# CPU.net
KiCad netlist of a schematic drawn in Altium Designer
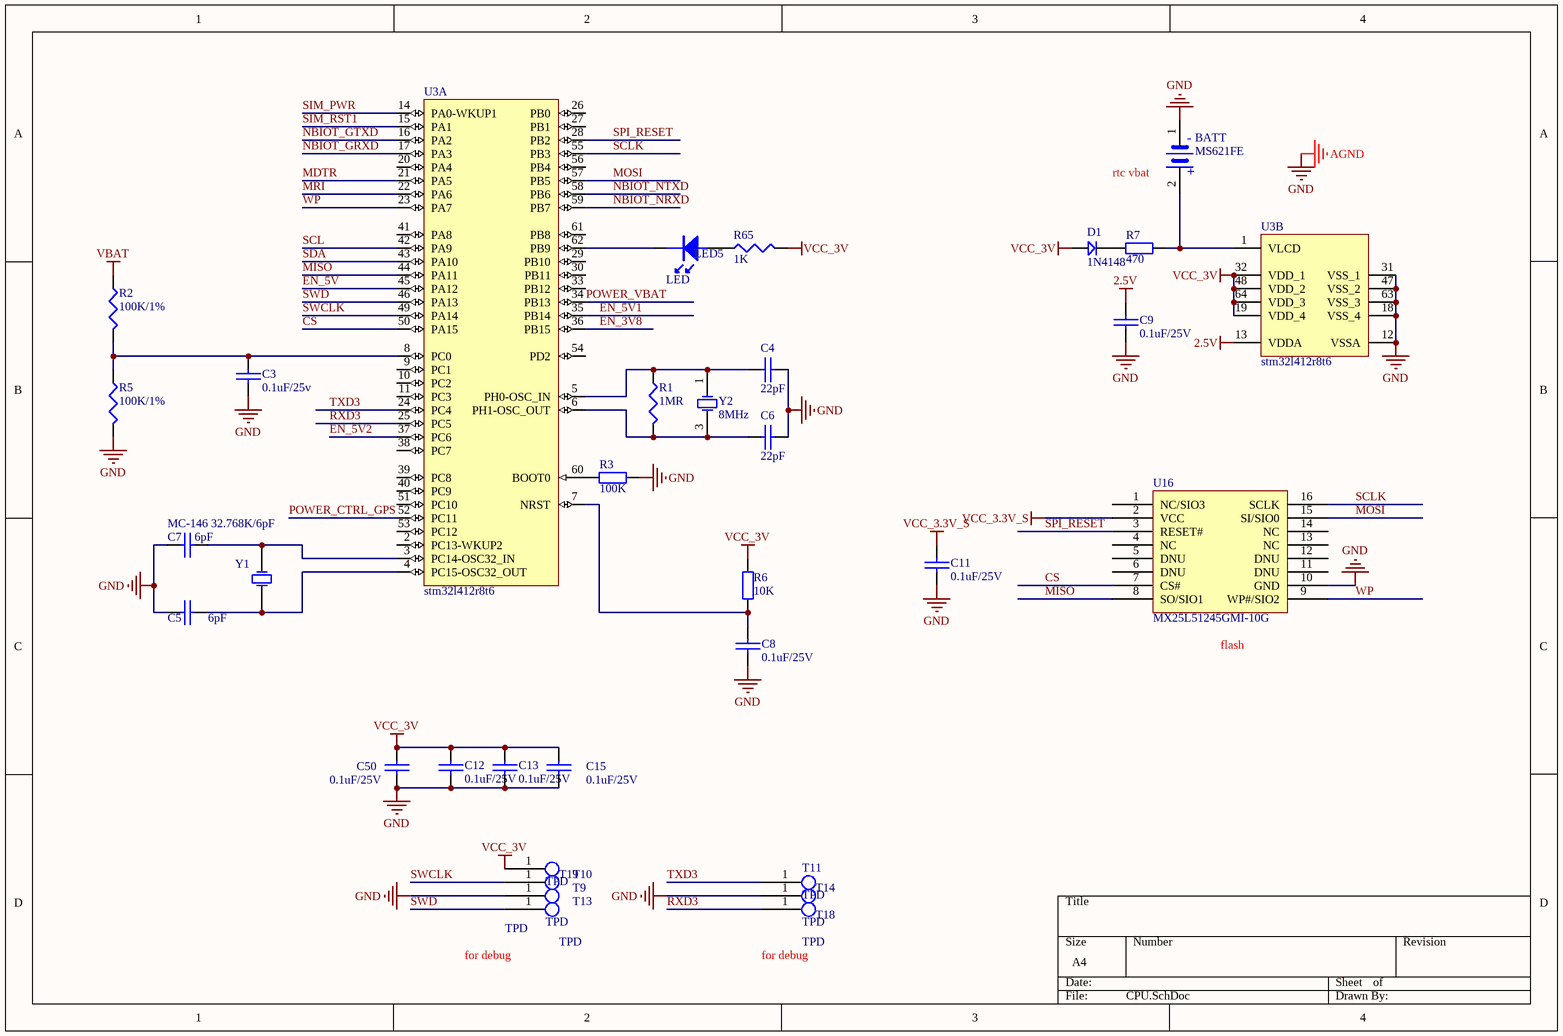
[diagram p0: CPU.SchDoc]

(export (version "E")
  (design (tool "Eeschema 10.0.6"))
  (components
    (comp (ref "BATT") (value "MS621FE") (footprint "MS621FE") (libsource (lib "Myself_1") (part "SBatery")))
    (comp (ref "C3")
      (value "0.1uF/25v")
      (footprint "0402c")
      (description "Capacitor")
      (libsource (lib "SM") (part "CAP"))
    )
    (comp (ref "C4")
      (value "22pF")
      (footprint "0402c")
      (description "Capacitor")
      (libsource (lib "SM") (part "CAP"))
    )
    (comp (ref "C5")
      (value "6pF")
      (footprint "0402c")
      (description "Capacitor")
      (libsource (lib "SM") (part "CAP"))
    )
    (comp (ref "C6")
      (value "22pF")
      (footprint "0402c")
      (description "Capacitor")
      (libsource (lib "SM") (part "CAP"))
    )
    (comp (ref "C7")
      (value "6pF")
      (footprint "0402c")
      (description "Capacitor")
      (libsource (lib "SM") (part "CAP"))
    )
    (comp (ref "C8")
      (value "0.1uF/25V")
      (footprint "0402C")
      (description "Capacitor")
      (libsource (lib "ZWLIntegrated_Library") (part "CAP"))
    )
    (comp (ref "C9")
      (value "0.1uF/25V")
      (footprint "0402C")
      (description "Capacitor")
      (libsource (lib "ZWLIntegrated_Library") (part "CAP"))
    )
    (comp (ref "C11")
      (value "0.1uF/25V")
      (footprint "0402C")
      (description "Capacitor")
      (libsource (lib "ZWLIntegrated_Library") (part "CAP"))
    )
    (comp (ref "C12")
      (value "0.1uF/25V")
      (footprint "0402C")
      (description "Capacitor")
      (libsource (lib "ZWLIntegrated_Library") (part "CAP"))
    )
    (comp (ref "C13")
      (value "0.1uF/25V")
      (footprint "0402C")
      (description "Capacitor")
      (libsource (lib "ZWLIntegrated_Library") (part "CAP"))
    )
    (comp (ref "C15")
      (value "0.1uF/25V")
      (footprint "0402C")
      (description "Capacitor")
      (libsource (lib "ZWLIntegrated_Library") (part "CAP"))
    )
    (comp (ref "C50")
      (value "0.1uF/25V")
      (footprint "0402C")
      (description "Capacitor")
      (libsource (lib "ZWLIntegrated_Library") (part "CAP"))
    )
    (comp (ref "D1")
      (value "1N4148")
      (footprint "DIODE_SOP")
      (libsource (lib "Explorer STM32F407封装库") (part "D"))
    )
    (comp (ref "LED5") (value "LED") (footprint "0603LED") (libsource (lib "我的元件库") (part "LED")))
    (comp (ref "R1")
      (value "1MR")
      (footprint "0402R")
      (description "Resistor")
      (fields (field (name "PUBLISHER") "Altium Limited"))
      (libsource (lib "SM") (part "Res3"))
    )
    (comp (ref "R2")
      (value "100K/1%")
      (footprint "0402R")
      (libsource (lib "ZWLIntegrated_Library") (part "RES1"))
    )
    (comp (ref "R3")
      (value "100K")
      (footprint "0402R")
      (description "Resistor")
      (fields (field (name "PUBLISHER") "Altium Limited"))
      (libsource (lib "") (part "Res2_1"))
    )
    (comp (ref "R5")
      (value "100K/1%")
      (footprint "0402R")
      (libsource (lib "ZWLIntegrated_Library") (part "RES1"))
    )
    (comp (ref "R6")
      (value "10K")
      (footprint "0402R")
      (description "Resistor")
      (fields (field (name "PUBLISHER") "Altium Limited"))
      (libsource (lib "Miscellaneous Devices") (part "Res2"))
    )
    (comp (ref "R7")
      (value "470")
      (footprint "0402R")
      (description "Resistor")
      (fields (field (name "PUBLISHER") "Altium Limited"))
      (libsource (lib "") (part "Res2_1"))
    )
    (comp (ref "R65")
      (value "1K")
      (footprint "0402R")
      (libsource (lib "ZWLIntegrated_Library") (part "RES1"))
    )
    (comp (ref "T9") (value "TPD") (footprint "Pcblib_20110825:TPd") (libsource (lib "stm32") (part "TPD")))
    (comp (ref "T10") (value "TPD") (footprint "Pcblib_20110825:TPd") (libsource (lib "stm32") (part "TPD")))
    (comp (ref "T11") (value "TPD") (footprint "Pcblib_20110825:TPd") (libsource (lib "stm32") (part "TPD")))
    (comp (ref "T13") (value "TPD") (footprint "Pcblib_20110825:TPd") (libsource (lib "stm32") (part "TPD")))
    (comp (ref "T14") (value "TPD") (footprint "Pcblib_20110825:TPd") (libsource (lib "stm32") (part "TPD")))
    (comp (ref "T18") (value "TPD") (footprint "Pcblib_20110825:TPd") (libsource (lib "stm32") (part "TPD")))
    (comp (ref "T19") (value "TPD") (footprint "Pcblib_20110825:TPd") (libsource (lib "stm32") (part "TPD")))
    (comp (ref "U3")
      (value "stm32l412r8t6")
      (footprint "LQFP-64")
      (fields (field (name "MANUFACTURER") "STMicroelectronics") (field (name "PARTNUMBER") "STM32L100R8T6"))
      (libsource (lib "STMicroelectronics STM32 L1") (part "STM32L100R8T6"))
    )
    (comp (ref "U16")
      (value "MX25L51245GMI-10G")
      (footprint "SOP127P1030X239-16N")
      (libsource (lib "stm32") (part "MX25L51245GMI-10G"))
    )
    (comp (ref "Y1")
      (value "MC-146 32.768K/6pF")
      (footprint "32.768K")
      (description "Crystal Oscillator")
      (fields (field (name "PUBLISHER") "Altium Limited"))
      (libsource (lib "Miscellaneous Devices") (part "XTAL"))
    )
    (comp (ref "Y2")
      (value "8MHz")
      (footprint "OSCILLATOR-3.2X2.5")
      (description "Crystal Oscillator")
      (fields (field (name "PUBLISHER") "Altium Limited"))
      (libsource (lib "") (part "XTAL_1"))
    )
  )
  (nets
    (net (code "1") (name "/CS") (class "Default")
      (node (ref "U16") (pin "7") (pinfunction "CS#_7") (pintype "passive"))
      (node (ref "U3") (pin "50") (pinfunction "PA15_50") (pintype "bidirectional"))
    )
    (net (code "2") (name "/EN_3V8") (class "Default")
      (node (ref "U3") (pin "36") (pinfunction "PB15_36") (pintype "bidirectional"))
    )
    (net (code "3") (name "/EN_5V") (class "Default")
      (node (ref "U3") (pin "45") (pinfunction "PA12_45") (pintype "bidirectional"))
    )
    (net (code "4") (name "/EN_5V1") (class "Default")
      (node (ref "U3") (pin "35") (pinfunction "PB14_35") (pintype "bidirectional"))
    )
    (net (code "5") (name "/EN_5V2") (class "Default")
      (node (ref "U3") (pin "37") (pinfunction "PC6_37") (pintype "bidirectional"))
    )
    (net (code "6") (name "/MDTR") (class "Default")
      (node (ref "U3") (pin "21") (pinfunction "PA5_21") (pintype "bidirectional"))
    )
    (net (code "7") (name "/MISO") (class "Default")
      (node (ref "U16") (pin "8") (pinfunction "SO/SIO1_8") (pintype "passive"))
      (node (ref "U3") (pin "44") (pinfunction "PA11_44") (pintype "bidirectional"))
    )
    (net (code "8") (name "/MOSI") (class "Default")
      (node (ref "U16") (pin "15") (pinfunction "SI/SIO0_15") (pintype "passive"))
      (node (ref "U3") (pin "57") (pinfunction "PB5_57") (pintype "bidirectional"))
    )
    (net (code "9") (name "/MRI") (class "Default")
      (node (ref "U3") (pin "22") (pinfunction "PA6_22") (pintype "bidirectional"))
    )
    (net (code "10") (name "/NBIOT_GRXD") (class "Default")
      (node (ref "U3") (pin "17") (pinfunction "PA3_17") (pintype "bidirectional"))
    )
    (net (code "11") (name "/NBIOT_GTXD") (class "Default")
      (node (ref "U3") (pin "16") (pinfunction "PA2_16") (pintype "bidirectional"))
    )
    (net (code "12") (name "/NBIOT_NRXD") (class "Default")
      (node (ref "U3") (pin "59") (pinfunction "PB7_59") (pintype "bidirectional"))
    )
    (net (code "13") (name "/NBIOT_NTXD") (class "Default")
      (node (ref "U3") (pin "58") (pinfunction "PB6_58") (pintype "bidirectional"))
    )
    (net (code "14") (name "/POWER_CTRL_GPS") (class "Default")
      (node (ref "U3") (pin "52") (pinfunction "PC11_52") (pintype "bidirectional"))
    )
    (net (code "15") (name "/POWER_VBAT") (class "Default")
      (node (ref "U3") (pin "34") (pinfunction "PB13_34") (pintype "bidirectional"))
    )
    (net (code "16") (name "/RXD3") (class "Default")
      (node (ref "T18") (pin "1") (pintype "passive"))
      (node (ref "U3") (pin "25") (pinfunction "PC5_25") (pintype "bidirectional"))
    )
    (net (code "17") (name "/SCL") (class "Default")
      (node (ref "U3") (pin "42") (pinfunction "PA9_42") (pintype "bidirectional"))
    )
    (net (code "18") (name "/SCLK") (class "Default")
      (node (ref "U16") (pin "16") (pinfunction "SCLK_16") (pintype "passive"))
      (node (ref "U3") (pin "55") (pinfunction "PB3_55") (pintype "bidirectional"))
    )
    (net (code "19") (name "/SDA") (class "Default")
      (node (ref "U3") (pin "43") (pinfunction "PA10_43") (pintype "bidirectional"))
    )
    (net (code "20") (name "/SIM_PWR") (class "Default")
      (node (ref "U3") (pin "14") (pinfunction "PA0-WKUP1_14") (pintype "bidirectional"))
    )
    (net (code "21") (name "/SIM_RST1") (class "Default")
      (node (ref "U3") (pin "15") (pinfunction "PA1_15") (pintype "bidirectional"))
    )
    (net (code "22") (name "/SPI_RESET") (class "Default")
      (node (ref "U16") (pin "3") (pinfunction "RESET#_3") (pintype "passive"))
      (node (ref "U3") (pin "28") (pinfunction "PB2_28") (pintype "bidirectional"))
    )
    (net (code "23") (name "/SWCLK") (class "Default")
      (node (ref "T10") (pin "1") (pintype "passive"))
      (node (ref "U3") (pin "49") (pinfunction "PA14_49") (pintype "bidirectional"))
    )
    (net (code "24") (name "/SWD") (class "Default")
      (node (ref "T9") (pin "1") (pintype "passive"))
      (node (ref "U3") (pin "46") (pinfunction "PA13_46") (pintype "bidirectional"))
    )
    (net (code "25") (name "/TXD3") (class "Default")
      (node (ref "T11") (pin "1") (pintype "passive"))
      (node (ref "U3") (pin "24") (pinfunction "PC4_24") (pintype "bidirectional"))
    )
    (net (code "26") (name "/WP") (class "Default")
      (node (ref "U16") (pin "9") (pinfunction "WP#/SIO2_9") (pintype "passive"))
      (node (ref "U3") (pin "23") (pinfunction "PA7_23") (pintype "bidirectional"))
    )
    (net (code "27") (name "2.5V") (class "Default")
      (node (ref "C9") (pin "2") (pinfunction "2_2") (pintype "passive"))
      (node (ref "U3") (pin "13") (pinfunction "VDDA_13") (pintype "power_in"))
    )
    (net (code "28") (name "AGND") (class "Default")
      (node (ref "BATT") (pin "1") (pinfunction "1_1") (pintype "passive"))
      (node (ref "C11") (pin "1") (pinfunction "1_1") (pintype "passive"))
      (node (ref "C12") (pin "1") (pinfunction "1_1") (pintype "passive"))
      (node (ref "C13") (pin "1") (pinfunction "1_1") (pintype "passive"))
      (node (ref "C15") (pin "1") (pinfunction "1_1") (pintype "passive"))
      (node (ref "C3") (pin "2") (pinfunction "2_2") (pintype "passive"))
      (node (ref "C4") (pin "1") (pinfunction "1_1") (pintype "passive"))
      (node (ref "C5") (pin "2") (pinfunction "2_2") (pintype "passive"))
      (node (ref "C50") (pin "1") (pinfunction "1_1") (pintype "passive"))
      (node (ref "C6") (pin "1") (pinfunction "1_1") (pintype "passive"))
      (node (ref "C7") (pin "2") (pinfunction "2_2") (pintype "passive"))
      (node (ref "C8") (pin "1") (pinfunction "1_1") (pintype "passive"))
      (node (ref "C9") (pin "1") (pinfunction "1_1") (pintype "passive"))
      (node (ref "R3") (pin "2") (pinfunction "2_2") (pintype "passive"))
      (node (ref "R5") (pin "2") (pinfunction "2_2") (pintype "passive"))
      (node (ref "T13") (pin "1") (pintype "passive"))
      (node (ref "T14") (pin "1") (pintype "passive"))
      (node (ref "U16") (pin "10") (pinfunction "GND_10") (pintype "passive"))
      (node (ref "U3") (pin "12") (pinfunction "VSSA_12") (pintype "power_in"))
      (node (ref "U3") (pin "18") (pinfunction "VSS_4_18") (pintype "power_in"))
      (node (ref "U3") (pin "31") (pinfunction "VSS_1_31") (pintype "power_in"))
      (node (ref "U3") (pin "47") (pinfunction "VSS_2_47") (pintype "power_in"))
      (node (ref "U3") (pin "63") (pinfunction "VSS_3_63") (pintype "power_in"))
    )
    (net (code "29") (name "Net-(D1-Pad2)") (class "Default")
      (node (ref "D1") (pin "2") (pintype "passive"))
      (node (ref "R7") (pin "1") (pinfunction "1_1") (pintype "passive"))
    )
    (net (code "30") (name "Net-(LED5-Pad1)") (class "Default")
      (node (ref "LED5") (pin "1") (pinfunction "1_1") (pintype "passive"))
      (node (ref "R65") (pin "1") (pinfunction "1_1") (pintype "passive"))
    )
    (net (code "31") (name "Net-(U3A-BOOT0)") (class "Default")
      (node (ref "R3") (pin "1") (pinfunction "1_1") (pintype "passive"))
      (node (ref "U3") (pin "60") (pinfunction "BOOT0_60") (pintype "input"))
    )
    (net (code "32") (name "Net-(U3A-NRST)") (class "Default")
      (node (ref "C8") (pin "2") (pinfunction "2_2") (pintype "passive"))
      (node (ref "R6") (pin "2") (pinfunction "2_2") (pintype "passive"))
      (node (ref "U3") (pin "7") (pinfunction "NRST_7") (pintype "bidirectional"))
    )
    (net (code "33") (name "Net-(U3A-PB9)") (class "Default")
      (node (ref "LED5") (pin "2") (pinfunction "2_2") (pintype "passive"))
      (node (ref "U3") (pin "62") (pinfunction "PB9_62") (pintype "bidirectional"))
    )
    (net (code "34") (name "Net-(U3A-PC0)") (class "Default")
      (node (ref "C3") (pin "1") (pinfunction "1_1") (pintype "passive"))
      (node (ref "R2") (pin "2") (pinfunction "2_2") (pintype "passive"))
      (node (ref "R5") (pin "1") (pinfunction "1_1") (pintype "passive"))
      (node (ref "U3") (pin "8") (pinfunction "PC0_8") (pintype "bidirectional"))
    )
    (net (code "35") (name "Net-(U3A-PC14-OSC32_IN)") (class "Default")
      (node (ref "C7") (pin "1") (pinfunction "1_1") (pintype "passive"))
      (node (ref "U3") (pin "3") (pinfunction "PC14-OSC32_IN_3") (pintype "bidirectional"))
      (node (ref "Y1") (pin "1") (pinfunction "OSC1_1") (pintype "passive"))
    )
    (net (code "36") (name "Net-(U3A-PC15-OSC32_OUT)") (class "Default")
      (node (ref "C5") (pin "1") (pinfunction "1_1") (pintype "passive"))
      (node (ref "U3") (pin "4") (pinfunction "PC15-OSC32_OUT_4") (pintype "bidirectional"))
      (node (ref "Y1") (pin "2") (pinfunction "OSC2_2") (pintype "passive"))
    )
    (net (code "37") (name "Net-(U3A-PH0-OSC_IN)") (class "Default")
      (node (ref "C4") (pin "2") (pinfunction "2_2") (pintype "passive"))
      (node (ref "R1") (pin "1") (pinfunction "1_1") (pintype "passive"))
      (node (ref "U3") (pin "5") (pinfunction "PH0-OSC_IN_5") (pintype "bidirectional"))
      (node (ref "Y2") (pin "1") (pinfunction "OSC1_1") (pintype "passive"))
    )
    (net (code "38") (name "Net-(U3A-PH1-OSC_OUT)") (class "Default")
      (node (ref "C6") (pin "2") (pinfunction "2_2") (pintype "passive"))
      (node (ref "R1") (pin "2") (pinfunction "2_2") (pintype "passive"))
      (node (ref "U3") (pin "6") (pinfunction "PH1-OSC_OUT_6") (pintype "bidirectional"))
      (node (ref "Y2") (pin "3") (pinfunction "OSC2_3") (pintype "passive"))
    )
    (net (code "39") (name "Net-(U3B-VLCD)") (class "Default")
      (node (ref "BATT") (pin "2") (pinfunction "2_2") (pintype "passive"))
      (node (ref "R7") (pin "2") (pinfunction "2_2") (pintype "passive"))
      (node (ref "U3") (pin "1") (pinfunction "VLCD_1") (pintype "power_in"))
    )
    (net (code "40") (name "VBAT") (class "Default")
      (node (ref "R2") (pin "1") (pinfunction "1_1") (pintype "passive"))
    )
    (net (code "41") (name "VCC_3.3V_S") (class "Default")
      (node (ref "C11") (pin "2") (pinfunction "2_2") (pintype "passive"))
      (node (ref "U16") (pin "2") (pinfunction "VCC_2") (pintype "passive"))
    )
    (net (code "42") (name "VCC_3V") (class "Default")
      (node (ref "C12") (pin "2") (pinfunction "2_2") (pintype "passive"))
      (node (ref "C13") (pin "2") (pinfunction "2_2") (pintype "passive"))
      (node (ref "C15") (pin "2") (pinfunction "2_2") (pintype "passive"))
      (node (ref "C50") (pin "2") (pinfunction "2_2") (pintype "passive"))
      (node (ref "D1") (pin "1") (pintype "passive"))
      (node (ref "R6") (pin "1") (pinfunction "1_1") (pintype "passive"))
      (node (ref "R65") (pin "2") (pinfunction "2_2") (pintype "passive"))
      (node (ref "T19") (pin "1") (pintype "passive"))
      (node (ref "U3") (pin "19") (pinfunction "VDD_4_19") (pintype "power_in"))
      (node (ref "U3") (pin "32") (pinfunction "VDD_1_32") (pintype "power_in"))
      (node (ref "U3") (pin "48") (pinfunction "VDD_2_48") (pintype "power_in"))
      (node (ref "U3") (pin "64") (pinfunction "VDD_3_64") (pintype "power_in"))
    )
    (net (code "43") (name "unconnected-(U3A-PA4-Pad20)") (class "Default")
      (node (ref "U3") (pin "20") (pinfunction "PA4_20") (pintype "bidirectional"))
    )
    (net (code "44") (name "unconnected-(U3A-PA8-Pad41)") (class "Default")
      (node (ref "U3") (pin "41") (pinfunction "PA8_41") (pintype "bidirectional"))
    )
    (net (code "45") (name "unconnected-(U3A-PB0-Pad26)") (class "Default")
      (node (ref "U3") (pin "26") (pinfunction "PB0_26") (pintype "bidirectional"))
    )
    (net (code "46") (name "unconnected-(U3A-PB1-Pad27)") (class "Default")
      (node (ref "U3") (pin "27") (pinfunction "PB1_27") (pintype "bidirectional"))
    )
    (net (code "47") (name "unconnected-(U3A-PB4-Pad56)") (class "Default")
      (node (ref "U3") (pin "56") (pinfunction "PB4_56") (pintype "bidirectional"))
    )
    (net (code "48") (name "unconnected-(U3A-PB8-Pad61)") (class "Default")
      (node (ref "U3") (pin "61") (pinfunction "PB8_61") (pintype "bidirectional"))
    )
    (net (code "49") (name "unconnected-(U3A-PB10-Pad29)") (class "Default")
      (node (ref "U3") (pin "29") (pinfunction "PB10_29") (pintype "bidirectional"))
    )
    (net (code "50") (name "unconnected-(U3A-PB11-Pad30)") (class "Default")
      (node (ref "U3") (pin "30") (pinfunction "PB11_30") (pintype "bidirectional"))
    )
    (net (code "51") (name "unconnected-(U3A-PB12-Pad33)") (class "Default")
      (node (ref "U3") (pin "33") (pinfunction "PB12_33") (pintype "bidirectional"))
    )
    (net (code "52") (name "unconnected-(U3A-PC1-Pad9)") (class "Default")
      (node (ref "U3") (pin "9") (pinfunction "PC1_9") (pintype "bidirectional"))
    )
    (net (code "53") (name "unconnected-(U3A-PC2-Pad10)") (class "Default")
      (node (ref "U3") (pin "10") (pinfunction "PC2_10") (pintype "bidirectional"))
    )
    (net (code "54") (name "unconnected-(U3A-PC3-Pad11)") (class "Default")
      (node (ref "U3") (pin "11") (pinfunction "PC3_11") (pintype "bidirectional"))
    )
    (net (code "55") (name "unconnected-(U3A-PC7-Pad38)") (class "Default")
      (node (ref "U3") (pin "38") (pinfunction "PC7_38") (pintype "bidirectional"))
    )
    (net (code "56") (name "unconnected-(U3A-PC8-Pad39)") (class "Default")
      (node (ref "U3") (pin "39") (pinfunction "PC8_39") (pintype "bidirectional"))
    )
    (net (code "57") (name "unconnected-(U3A-PC9-Pad40)") (class "Default")
      (node (ref "U3") (pin "40") (pinfunction "PC9_40") (pintype "bidirectional"))
    )
    (net (code "58") (name "unconnected-(U3A-PC10-Pad51)") (class "Default")
      (node (ref "U3") (pin "51") (pinfunction "PC10_51") (pintype "bidirectional"))
    )
    (net (code "59") (name "unconnected-(U3A-PC12-Pad53)") (class "Default")
      (node (ref "U3") (pin "53") (pinfunction "PC12_53") (pintype "bidirectional"))
    )
    (net (code "60") (name "unconnected-(U3A-PC13-WKUP2-Pad2)") (class "Default")
      (node (ref "U3") (pin "2") (pinfunction "PC13-WKUP2_2") (pintype "bidirectional"))
    )
    (net (code "61") (name "unconnected-(U3A-PD2-Pad54)") (class "Default")
      (node (ref "U3") (pin "54") (pinfunction "PD2_54") (pintype "bidirectional"))
    )
    (net (code "62") (name "unconnected-(U16-DNU-Pad5)") (class "Default")
      (node (ref "U16") (pin "5") (pinfunction "DNU_5") (pintype "passive"))
    )
    (net (code "63") (name "unconnected-(U16-DNU-Pad6)") (class "Default")
      (node (ref "U16") (pin "6") (pinfunction "DNU_6") (pintype "passive"))
    )
    (net (code "64") (name "unconnected-(U16-DNU-Pad11)") (class "Default")
      (node (ref "U16") (pin "11") (pinfunction "DNU_11") (pintype "passive"))
    )
    (net (code "65") (name "unconnected-(U16-DNU-Pad12)") (class "Default")
      (node (ref "U16") (pin "12") (pinfunction "DNU_12") (pintype "passive"))
    )
    (net (code "66") (name "unconnected-(U16-NC-Pad4)") (class "Default")
      (node (ref "U16") (pin "4") (pinfunction "NC_4") (pintype "passive"))
    )
    (net (code "67") (name "unconnected-(U16-NC-Pad13)") (class "Default")
      (node (ref "U16") (pin "13") (pinfunction "NC_13") (pintype "passive"))
    )
    (net (code "68") (name "unconnected-(U16-NC-Pad14)") (class "Default")
      (node (ref "U16") (pin "14") (pinfunction "NC_14") (pintype "passive"))
    )
    (net (code "69") (name "unconnected-(U16-NC{slash}SIO3-Pad1)") (class "Default")
      (node (ref "U16") (pin "1") (pinfunction "NC/SIO3_1") (pintype "passive"))
    )
  )
)
